# ASL2111.net
KiCad netlist of a schematic drawn in EAGLE
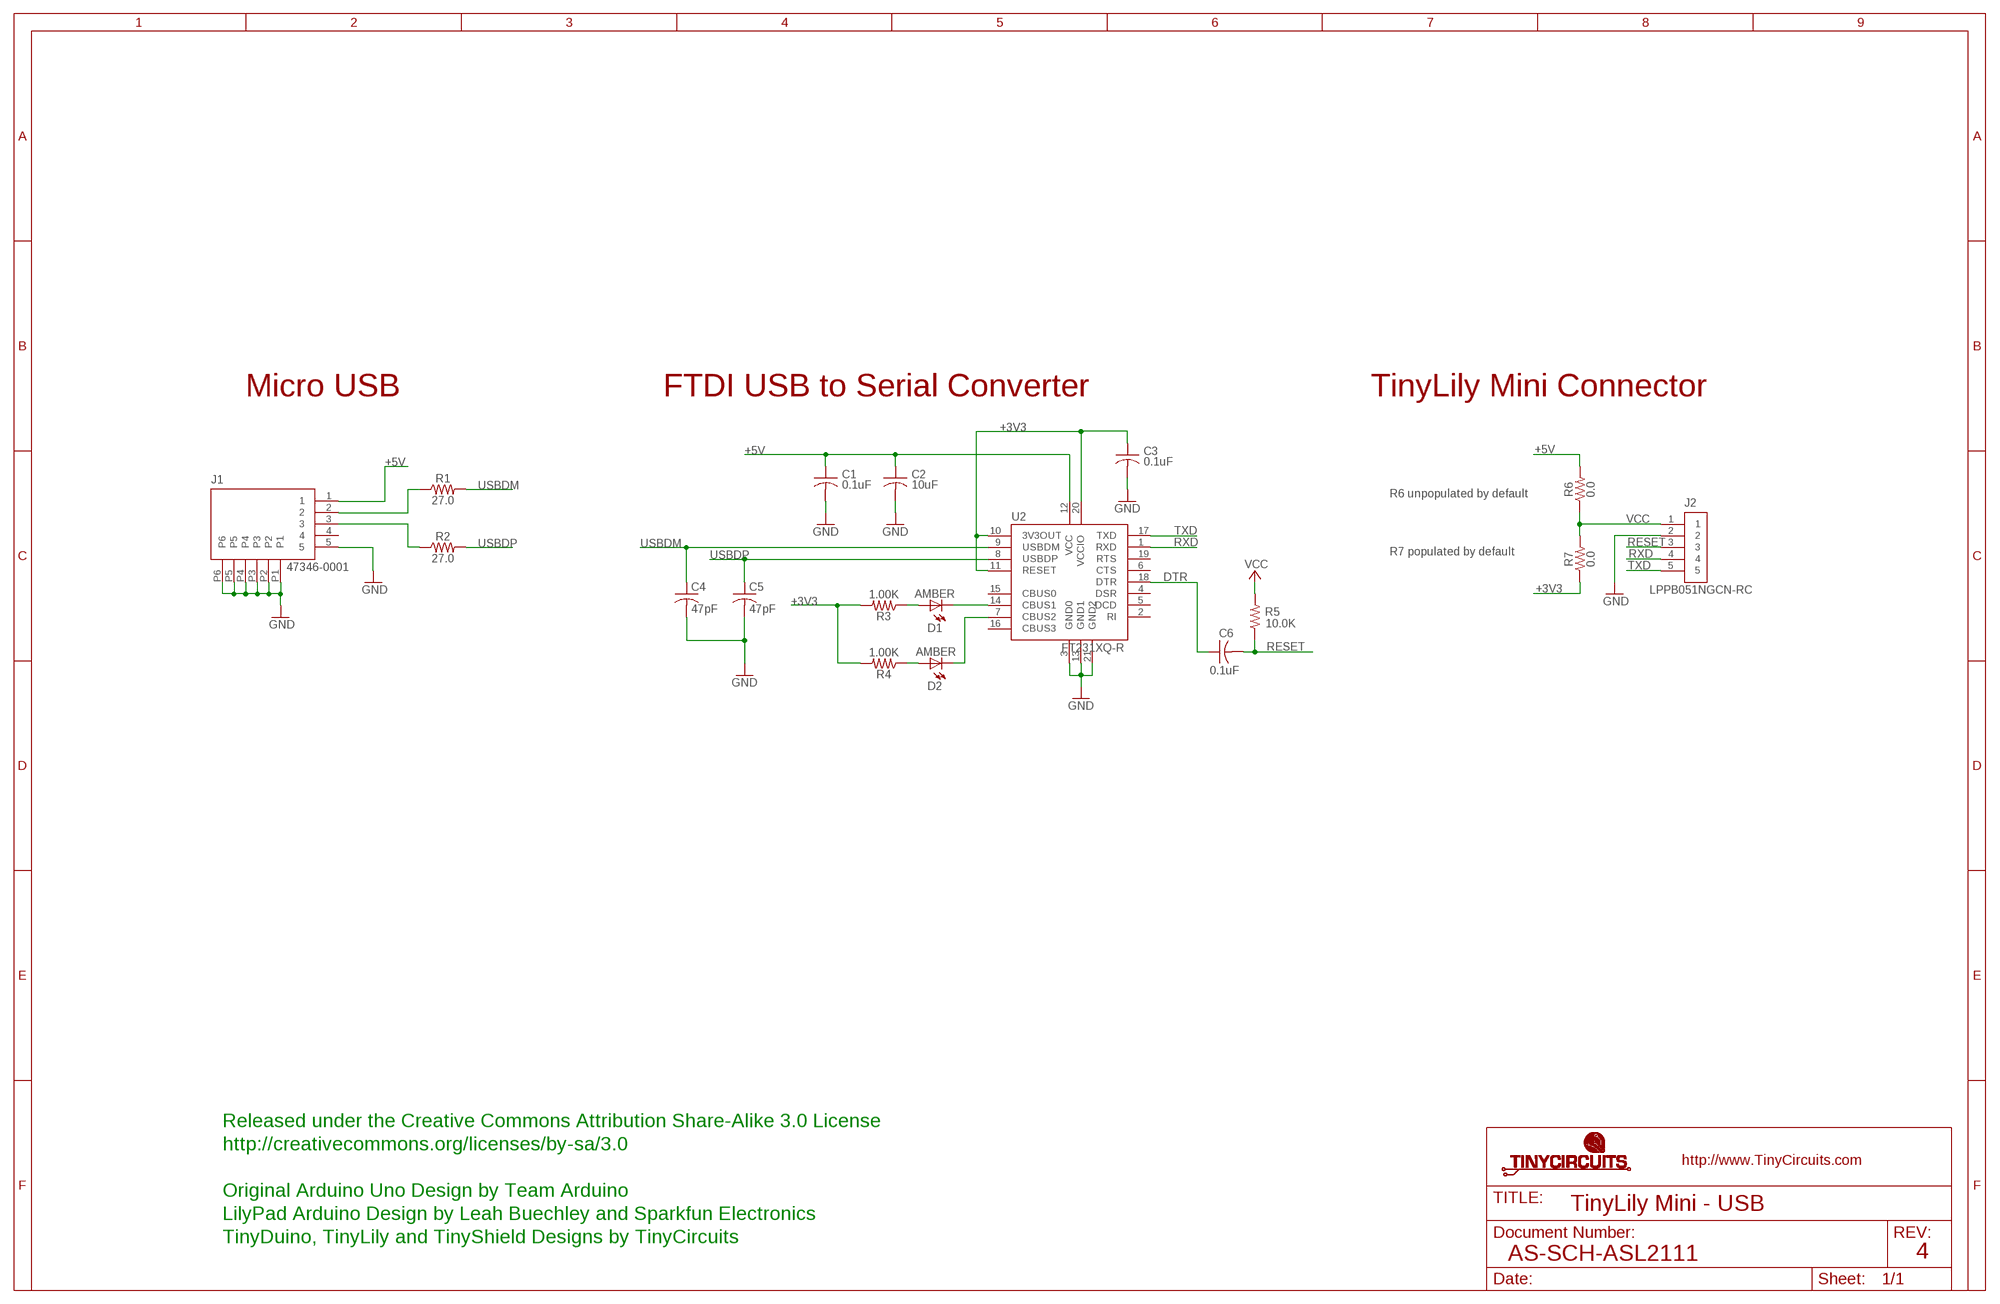
[diagram p0: schematic, sheet 1]

(export (version "E")
  (design (tool "Eeschema 10.0.6"))
  (components
    (comp (ref "C1")
      (value "0.1uF")
      (footprint "eagle-import:C0402")
      (fields (field (name "PARTNO") "AS-ITM-00008"))
      (libsource (lib "eagle-import") (part "AS-ITM-00008"))
    )
    (comp (ref "C2")
      (value "10uF")
      (footprint "eagle-import:C0603")
      (fields (field (name "PARTNO") "AS-ITM-00002"))
      (libsource (lib "eagle-import") (part "AS-ITM-00002"))
    )
    (comp (ref "C3")
      (value "0.1uF")
      (footprint "eagle-import:C0402")
      (fields (field (name "PARTNO") "AS-ITM-00008") (field (name "PARTNO_1") "AS-ITM-00008"))
      (libsource (lib "eagle-import") (part "AS-ITM-00008"))
    )
    (comp (ref "C4")
      (value "47pF")
      (footprint "eagle-import:0402")
      (fields (field (name "PARTNO") "AS-ITM-00241") (field (name "PARTNO_1") "AS-ITM-00241"))
      (libsource (lib "eagle-import") (part "AS-ITM-00241"))
    )
    (comp (ref "C5")
      (value "47pF")
      (footprint "eagle-import:0402")
      (fields (field (name "PARTNO") "AS-ITM-00241") (field (name "PARTNO_1") "AS-ITM-00241"))
      (libsource (lib "eagle-import") (part "AS-ITM-00241"))
    )
    (comp (ref "C6")
      (value "0.1uF")
      (footprint "eagle-import:C0402")
      (fields (field (name "PARTNO") "AS-ITM-00008") (field (name "PARTNO_1") "AS-ITM-00008"))
      (libsource (lib "eagle-import") (part "AS-ITM-00008"))
    )
    (comp (ref "D1")
      (value "AMBER")
      (footprint "eagle-import:LNJ_LED")
      (fields (field (name "PARTNO") "AS-ITM-00026"))
      (libsource (lib "eagle-import") (part "AS-ITM-00026"))
    )
    (comp (ref "D2")
      (value "AMBER")
      (footprint "eagle-import:LNJ_LED")
      (fields (field (name "PARTNO") "AS-ITM-00026"))
      (libsource (lib "eagle-import") (part "AS-ITM-00026"))
    )
    (comp (ref "J1")
      (value "47346-0001")
      (footprint "eagle-import:MICRO_USB")
      (fields (field (name "PARTNO") "AS-ITM-00021") (field (name "PARTNO_1") "AS-ITM-00021"))
      (libsource (lib "eagle-import") (part "AS-ITM-00021"))
    )
    (comp (ref "J2")
      (value "LPPB051NGCN-RC")
      (footprint "eagle-import:1X5_.05_RA_TH_RECPT")
      (fields (field (name "PARTNO") "AS-ITM-00037"))
      (libsource (lib "eagle-import") (part "AS-ITM-00037"))
    )
    (comp (ref "R1")
      (value "27.0")
      (footprint "eagle-import:0402")
      (libsource (lib "eagle-import") (part "AS-ITM-00240"))
    )
    (comp (ref "R2")
      (value "27.0")
      (footprint "eagle-import:0402")
      (libsource (lib "eagle-import") (part "AS-ITM-00240"))
    )
    (comp (ref "R3")
      (value "1.00K")
      (footprint "eagle-import:0402")
      (fields (field (name "PARTNO") "AS-ITM-00003"))
      (libsource (lib "eagle-import") (part "AS-ITM-00003"))
    )
    (comp (ref "R4")
      (value "1.00K")
      (footprint "eagle-import:0402")
      (fields (field (name "PARTNO") "AS-ITM-00003"))
      (libsource (lib "eagle-import") (part "AS-ITM-00003"))
    )
    (comp (ref "R5")
      (value "10.0K")
      (footprint "eagle-import:0402")
      (fields (field (name "PARTNO") "AS-ITM-00032"))
      (libsource (lib "eagle-import") (part "AS-ITM-00032"))
    )
    (comp (ref "R6")
      (value "0.0")
      (footprint "eagle-import:0402")
      (fields (field (name "PARTNO") "AS-ITM-00076"))
      (libsource (lib "eagle-import") (part "AS-ITM-00076"))
    )
    (comp (ref "R7")
      (value "0.0")
      (footprint "eagle-import:0402")
      (fields (field (name "PARTNO") "AS-ITM-00076"))
      (libsource (lib "eagle-import") (part "AS-ITM-00076"))
    )
    (comp (ref "U2")
      (value "FT231XQ-R")
      (footprint "eagle-import:QFN20")
      (fields (field (name "PARTNO") "AS-ITM-00223"))
      (libsource (lib "eagle-import") (part "AS-ITM-00223"))
    )
  )
  (nets
    (net (code "1") (name "/+3V3") (class "Default")
      (node (ref "C3") (pin "1") (pinfunction "1_1") (pintype "passive"))
      (node (ref "R3") (pin "2") (pinfunction "2_2") (pintype "passive"))
      (node (ref "R4") (pin "2") (pinfunction "2_2") (pintype "passive"))
      (node (ref "R7") (pin "1") (pinfunction "1_1") (pintype "passive"))
      (node (ref "U2") (pin "10") (pinfunction "3V3OUT_10") (pintype "bidirectional"))
      (node (ref "U2") (pin "11") (pinfunction "RESET_11") (pintype "bidirectional"))
      (node (ref "U2") (pin "20") (pinfunction "VCCIO_20") (pintype "bidirectional"))
    )
    (net (code "2") (name "/+5V") (class "Default")
      (node (ref "C1") (pin "1") (pinfunction "1_1") (pintype "passive"))
      (node (ref "C2") (pin "1") (pinfunction "1_1") (pintype "passive"))
      (node (ref "J1") (pin "1") (pinfunction "1_1") (pintype "bidirectional"))
      (node (ref "R6") (pin "2") (pinfunction "2_2") (pintype "passive"))
      (node (ref "U2") (pin "12") (pinfunction "VCC_12") (pintype "bidirectional"))
    )
    (net (code "3") (name "/DTR") (class "Default")
      (node (ref "C6") (pin "1") (pinfunction "1_1") (pintype "passive"))
      (node (ref "U2") (pin "18") (pinfunction "DTR_18") (pintype "bidirectional"))
    )
    (net (code "4") (name "/RESET") (class "Default")
      (node (ref "C6") (pin "2") (pinfunction "2_2") (pintype "passive"))
      (node (ref "J2") (pin "3") (pinfunction "3_3") (pintype "bidirectional"))
      (node (ref "R5") (pin "1") (pinfunction "1_1") (pintype "passive"))
    )
    (net (code "5") (name "/RXD") (class "Default")
      (node (ref "J2") (pin "4") (pinfunction "4_4") (pintype "bidirectional"))
      (node (ref "U2") (pin "1") (pinfunction "RXD_1") (pintype "bidirectional"))
    )
    (net (code "6") (name "/TXD") (class "Default")
      (node (ref "J2") (pin "5") (pinfunction "5_5") (pintype "bidirectional"))
      (node (ref "U2") (pin "17") (pinfunction "TXD_17") (pintype "bidirectional"))
    )
    (net (code "7") (name "/USBDM") (class "Default")
      (node (ref "C4") (pin "1") (pinfunction "1_1") (pintype "passive"))
      (node (ref "R1") (pin "2") (pinfunction "2_2") (pintype "passive"))
      (node (ref "U2") (pin "9") (pinfunction "USBDM_9") (pintype "bidirectional"))
    )
    (net (code "8") (name "/USBDP") (class "Default")
      (node (ref "C5") (pin "1") (pinfunction "1_1") (pintype "passive"))
      (node (ref "R2") (pin "2") (pinfunction "2_2") (pintype "passive"))
      (node (ref "U2") (pin "8") (pinfunction "USBDP_8") (pintype "bidirectional"))
    )
    (net (code "9") (name "GND") (class "Default")
      (node (ref "C1") (pin "2") (pinfunction "2_2") (pintype "passive"))
      (node (ref "C2") (pin "2") (pinfunction "2_2") (pintype "passive"))
      (node (ref "C3") (pin "2") (pinfunction "2_2") (pintype "passive"))
      (node (ref "C4") (pin "2") (pinfunction "2_2") (pintype "passive"))
      (node (ref "C5") (pin "2") (pinfunction "2_2") (pintype "passive"))
      (node (ref "J1") (pin "5") (pinfunction "5_5") (pintype "bidirectional"))
      (node (ref "J1") (pin "P1") (pinfunction "P1_P1") (pintype "bidirectional"))
      (node (ref "J1") (pin "P2") (pinfunction "P2_P2") (pintype "bidirectional"))
      (node (ref "J1") (pin "P3") (pinfunction "P3_P3") (pintype "bidirectional"))
      (node (ref "J1") (pin "P4") (pinfunction "P4_P4") (pintype "bidirectional"))
      (node (ref "J1") (pin "P5") (pinfunction "P5_P5") (pintype "bidirectional"))
      (node (ref "J1") (pin "P6") (pinfunction "P6_P6") (pintype "bidirectional"))
      (node (ref "J2") (pin "2") (pinfunction "2_2") (pintype "bidirectional"))
      (node (ref "U2") (pin "13") (pinfunction "GND1_13") (pintype "bidirectional"))
      (node (ref "U2") (pin "21") (pinfunction "GND2_21") (pintype "bidirectional"))
      (node (ref "U2") (pin "3") (pinfunction "GND0_3") (pintype "bidirectional"))
    )
    (net (code "10") (name "Net-(D1-PadA)") (class "Default")
      (node (ref "D1") (pin "A") (pinfunction "A_A") (pintype "passive"))
      (node (ref "R3") (pin "1") (pinfunction "1_1") (pintype "passive"))
    )
    (net (code "11") (name "Net-(D2-PadA)") (class "Default")
      (node (ref "D2") (pin "A") (pinfunction "A_A") (pintype "passive"))
      (node (ref "R4") (pin "1") (pinfunction "1_1") (pintype "passive"))
    )
    (net (code "12") (name "Net-(J1-Pad2)") (class "Default")
      (node (ref "J1") (pin "2") (pinfunction "2_2") (pintype "bidirectional"))
      (node (ref "R1") (pin "1") (pinfunction "1_1") (pintype "passive"))
    )
    (net (code "13") (name "Net-(J1-Pad3)") (class "Default")
      (node (ref "J1") (pin "3") (pinfunction "3_3") (pintype "bidirectional"))
      (node (ref "R2") (pin "1") (pinfunction "1_1") (pintype "passive"))
    )
    (net (code "14") (name "Net-(U2-CBUS1)") (class "Default")
      (node (ref "D1") (pin "C") (pinfunction "C_C") (pintype "passive"))
      (node (ref "U2") (pin "14") (pinfunction "CBUS1_14") (pintype "bidirectional"))
    )
    (net (code "15") (name "Net-(U2-CBUS2)") (class "Default")
      (node (ref "D2") (pin "C") (pinfunction "C_C") (pintype "passive"))
      (node (ref "U2") (pin "7") (pinfunction "CBUS2_7") (pintype "bidirectional"))
    )
    (net (code "16") (name "VCC") (class "Default")
      (node (ref "J2") (pin "1") (pinfunction "1_1") (pintype "bidirectional"))
      (node (ref "R5") (pin "2") (pinfunction "2_2") (pintype "passive"))
      (node (ref "R6") (pin "1") (pinfunction "1_1") (pintype "passive"))
      (node (ref "R7") (pin "2") (pinfunction "2_2") (pintype "passive"))
    )
    (net (code "17") (name "unconnected-(J1-Pad4)") (class "Default")
      (node (ref "J1") (pin "4") (pinfunction "4_4") (pintype "bidirectional"))
    )
    (net (code "18") (name "unconnected-(U2-CBUS0-Pad15)") (class "Default")
      (node (ref "U2") (pin "15") (pinfunction "CBUS0_15") (pintype "bidirectional"))
    )
    (net (code "19") (name "unconnected-(U2-CBUS3-Pad16)") (class "Default")
      (node (ref "U2") (pin "16") (pinfunction "CBUS3_16") (pintype "bidirectional"))
    )
    (net (code "20") (name "unconnected-(U2-CTS-Pad6)") (class "Default")
      (node (ref "U2") (pin "6") (pinfunction "CTS_6") (pintype "bidirectional"))
    )
    (net (code "21") (name "unconnected-(U2-DCD-Pad5)") (class "Default")
      (node (ref "U2") (pin "5") (pinfunction "DCD_5") (pintype "bidirectional"))
    )
    (net (code "22") (name "unconnected-(U2-DSR-Pad4)") (class "Default")
      (node (ref "U2") (pin "4") (pinfunction "DSR_4") (pintype "bidirectional"))
    )
    (net (code "23") (name "unconnected-(U2-RI-Pad2)") (class "Default")
      (node (ref "U2") (pin "2") (pinfunction "RI_2") (pintype "bidirectional"))
    )
    (net (code "24") (name "unconnected-(U2-RTS-Pad19)") (class "Default")
      (node (ref "U2") (pin "19") (pinfunction "RTS_19") (pintype "bidirectional"))
    )
  )
)
